# Current_Sink.net
KiCad netlist of a schematic drawn in Altium Designer
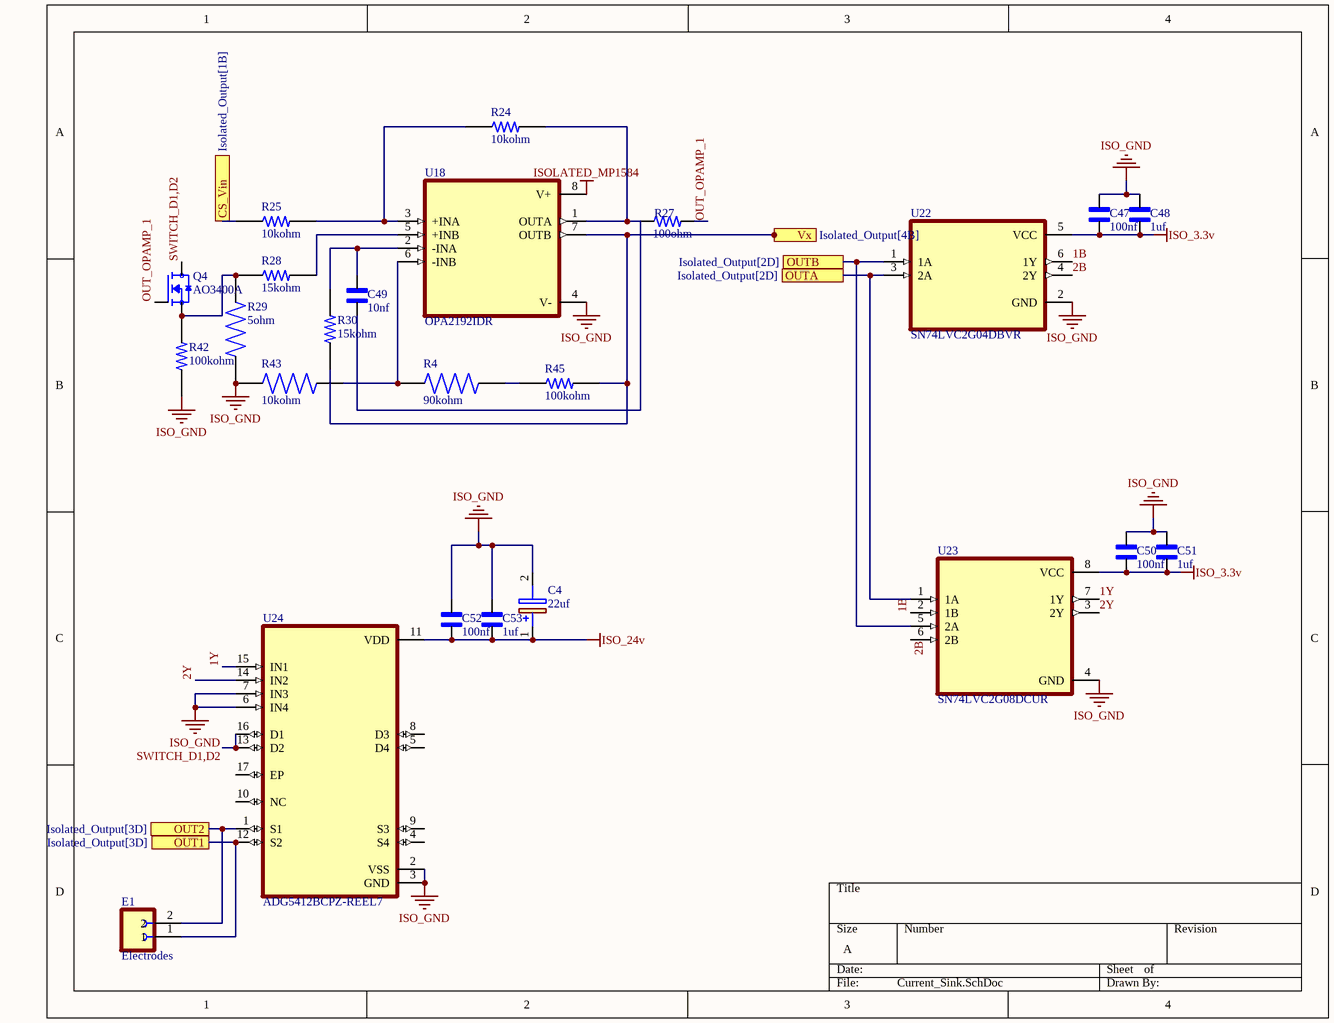
[diagram p0: Current_Sink.SchDoc]

(export (version "E")
  (design (tool "Eeschema 10.0.6"))
  (components
    (comp (ref "C4")
      (value "22uf")
      (footprint "SamacSys:CAPAE660X610N")
      (description "Capacitor Polarised")
      (fields
        (field (name "MANUFACTURER_PART_NUMBER") "HHXC500ARA220MF61G")
        (field (name "MOUSER PART NUMBER") "661-HHXC500A220MF61G")
      )
      (libsource (lib "*") (part "HHXC500ARA220MF61G"))
    )
    (comp (ref "C47")
      (value "100nf")
      (footprint "CAPC1608X90")
      (description "0603 1 nF 50 V Â±10 % Tolerance X7R Surface Mount Ceramic Capacitor")
      (fields (field (name "MF") "Yageo") (field (name "MP") "C0603KRX7R9BB102"))
      (libsource (lib "C0603KRX7R9BB102") (part "C0603KRX7R9BB102"))
    )
    (comp (ref "C48")
      (value "1uf")
      (footprint "CAPC1608X90")
      (description "0603 1 nF 50 V Â±10 % Tolerance X7R Surface Mount Ceramic Capacitor")
      (fields (field (name "MF") "Yageo") (field (name "MP") "C0603KRX7R9BB102"))
      (libsource (lib "C0603KRX7R9BB102") (part "C0603KRX7R9BB102"))
    )
    (comp (ref "C49")
      (value "10nf")
      (footprint "CAPC1608X90")
      (description "0603 1 nF 50 V Â±10 % Tolerance X7R Surface Mount Ceramic Capacitor")
      (fields (field (name "MF") "Yageo") (field (name "MP") "C0603KRX7R9BB102"))
      (libsource (lib "") (part "C0603KRX7R9BB102_1"))
    )
    (comp (ref "C50")
      (value "100nf")
      (footprint "CAPC1608X90")
      (description "0603 1 nF 50 V Â±10 % Tolerance X7R Surface Mount Ceramic Capacitor")
      (fields (field (name "MF") "Yageo") (field (name "MP") "C0603KRX7R9BB102"))
      (libsource (lib "C0603KRX7R9BB102") (part "C0603KRX7R9BB102"))
    )
    (comp (ref "C51")
      (value "1uf")
      (footprint "CAPC1608X90")
      (description "0603 1 nF 50 V Â±10 % Tolerance X7R Surface Mount Ceramic Capacitor")
      (fields (field (name "MF") "Yageo") (field (name "MP") "C0603KRX7R9BB102"))
      (libsource (lib "C0603KRX7R9BB102") (part "C0603KRX7R9BB102"))
    )
    (comp (ref "C52")
      (value "100nf")
      (footprint "CAPC1608X90")
      (description "0603 1 nF 50 V Â±10 % Tolerance X7R Surface Mount Ceramic Capacitor")
      (fields (field (name "MF") "Yageo") (field (name "MP") "C0603KRX7R9BB102"))
      (libsource (lib "C0603KRX7R9BB102") (part "C0603KRX7R9BB102"))
    )
    (comp (ref "C53")
      (value "1uf")
      (footprint "CAPC1608X90")
      (description "0603 1 nF 50 V Â±10 % Tolerance X7R Surface Mount Ceramic Capacitor")
      (fields (field (name "MF") "Yageo") (field (name "MP") "C0603KRX7R9BB102"))
      (libsource (lib "C0603KRX7R9BB102") (part "C0603KRX7R9BB102"))
    )
    (comp (ref "E1")
      (value "Electrodes")
      (footprint "JST_PHR-2")
      (description "PH Series 2 Position 2 mm Pitch Free Hanging Housing Connector")
      (fields (field (name "MP") "PHR-2"))
      (libsource (lib "PHR-2") (part "PHR-2"))
    )
    (comp (ref "Q4")
      (value "AO3400A")
      (footprint "SOT95P280X125-3N")
      (description "N-Channel 30 V 5.7A (Ta) 1.4W (Ta) Surface Mount SOT-23-3")
      (fields (field (name "MF") "Alpha & Omega Semiconductor"))
      (libsource (lib "AO3400A") (part "AO3400A"))
    )
    (comp (ref "R4")
      (value "90kohm")
      (footprint "RESC2012X65N")
      (description "5.11 Ohms Â±0.1% 0.25W, 1/4W Chip Resistor 0805 (2012 Metric) Automotive AEC-Q200 Thin Film")
      (fields (field (name "MF") "Stackpole Electronics Inc") (field (name "MP") "RNCF0805BTE5R11"))
      (libsource (lib "RNCF0805BTE5R11") (part "RNCF0805BTE5R11"))
    )
    (comp (ref "R24")
      (value "10kohm")
      (footprint "RESC1607X60N")
      (description "10 kOhms Â±5% 0.1W, 1/10W Chip Resistor 0603 (1608 Metric) Moisture Resistant Thick Film")
      (fields (field (name "MF") "Yageo") (field (name "MP") "RC0603JR-0710KL"))
      (libsource (lib "RC0603JR-0710KL") (part "RC0603JR-0710KL"))
    )
    (comp (ref "R25")
      (value "10kohm")
      (footprint "RESC1607X60N")
      (description "10 kOhms Â±5% 0.1W, 1/10W Chip Resistor 0603 (1608 Metric) Moisture Resistant Thick Film")
      (fields (field (name "MF") "Yageo") (field (name "MP") "RC0603JR-0710KL"))
      (libsource (lib "RC0603JR-0710KL") (part "RC0603JR-0710KL"))
    )
    (comp (ref "R27")
      (value "100ohm")
      (footprint "RESC1607X60N")
      (description "10 kOhms Â±5% 0.1W, 1/10W Chip Resistor 0603 (1608 Metric) Moisture Resistant Thick Film")
      (fields (field (name "MF") "Yageo") (field (name "MP") "RC0603JR-0710KL"))
      (libsource (lib "RC0603JR-0710KL") (part "RC0603JR-0710KL"))
    )
    (comp (ref "R28")
      (value "15kohm")
      (footprint "RESC1607X60N")
      (description "10 kOhms Â±5% 0.1W, 1/10W Chip Resistor 0603 (1608 Metric) Moisture Resistant Thick Film")
      (fields (field (name "MF") "Yageo") (field (name "MP") "RC0603JR-0710KL"))
      (libsource (lib "RC0603JR-0710KL") (part "RC0603JR-0710KL"))
    )
    (comp (ref "R29")
      (value "5ohm")
      (footprint "RESC2012X50N")
      (fields (field (name "MF") "Susumu") (field (name "MP") "RG2012V-103-P-T1"))
      (libsource (lib "RG2012V-103-P-T1") (part "RG2012V-103-P-T1"))
    )
    (comp (ref "R30")
      (value "15kohm")
      (footprint "RESC1607X60N")
      (description "10 kOhms Â±5% 0.1W, 1/10W Chip Resistor 0603 (1608 Metric) Moisture Resistant Thick Film")
      (fields (field (name "MF") "Yageo") (field (name "MP") "RC0603JR-0710KL"))
      (libsource (lib "RC0603JR-0710KL") (part "RC0603JR-0710KL"))
    )
    (comp (ref "R42")
      (value "100kohm")
      (footprint "RESC1607X60N")
      (description "10 kOhms Â±5% 0.1W, 1/10W Chip Resistor 0603 (1608 Metric) Moisture Resistant Thick Film")
      (fields (field (name "MF") "Yageo") (field (name "MP") "RC0603JR-0710KL"))
      (libsource (lib "RC0603JR-0710KL") (part "RC0603JR-0710KL"))
    )
    (comp (ref "R43")
      (value "10kohm")
      (footprint "RESC2012X50N")
      (fields (field (name "MF") "Susumu") (field (name "MP") "RG2012V-103-P-T1"))
      (libsource (lib "RG2012V-103-P-T1") (part "RG2012V-103-P-T1"))
    )
    (comp (ref "R45")
      (value "100kohm")
      (footprint "RESC1607X60N")
      (description "10 kOhms Â±5% 0.1W, 1/10W Chip Resistor 0603 (1608 Metric) Moisture Resistant Thick Film")
      (fields (field (name "MF") "Yageo") (field (name "MP") "RC0603JR-0710KL"))
      (libsource (lib "RC0603JR-0710KL") (part "RC0603JR-0710KL"))
    )
    (comp (ref "U18")
      (value "OPA2192IDR")
      (footprint "SOIC127P599X175-8N")
      (description "36-V, Precision, RRIO, Low Offset Voltage, Low Input Bias Current Op Amp With e-trim")
      (fields (field (name "MF") "Texas Instruments"))
      (libsource (lib "OPA2192IDR") (part "OPA2192IDR"))
    )
    (comp (ref "U22")
      (value "SN74LVC2G04DBVR")
      (footprint "SOT95P280X145-6N")
      (description "2-ch, 1.65-V to 5.5-V inverters")
      (fields (field (name "MF") "Texas Instruments"))
      (libsource (lib "SN74LVC2G04DBVR") (part "SN74LVC2G04DBVR"))
    )
    (comp (ref "U23")
      (value "SN74LVC2G08DCUR")
      (footprint "SOP50P310X90-8N")
      (description "2-ch, 2-input, 1.65-V to 5.5-V AND gates")
      (fields (field (name "MF") "Texas Instruments"))
      (libsource (lib "SN74LVC2G08DCUR") (part "SN74LVC2G08DCUR"))
    )
    (comp (ref "U24")
      (value "ADG5412BCPZ-REEL7")
      (footprint "QFN65P400X400X80-17N")
      (description "High Voltage Latch-Up Proof, Quad SPST Switches")
      (fields (field (name "MF") "Analog Devices"))
      (libsource (lib "ADG5412BCPZ-REEL7") (part "ADG5412BCPZ-REEL7"))
    )
  )
  (nets
    (net (code "1") (name "/1B") (class "Default")
      (node (ref "U22") (pin "6") (pinfunction "1Y_6") (pintype "output"))
      (node (ref "U23") (pin "2") (pinfunction "1B_2") (pintype "input"))
    )
    (net (code "2") (name "/1Y") (class "Default")
      (node (ref "U23") (pin "7") (pinfunction "1Y_7") (pintype "output"))
      (node (ref "U24") (pin "15") (pinfunction "IN1_15") (pintype "input"))
    )
    (net (code "3") (name "/2B") (class "Default")
      (node (ref "U22") (pin "4") (pinfunction "2Y_4") (pintype "output"))
      (node (ref "U23") (pin "6") (pinfunction "2B_6") (pintype "input"))
    )
    (net (code "4") (name "/2Y") (class "Default")
      (node (ref "U23") (pin "3") (pinfunction "2Y_3") (pintype "output"))
      (node (ref "U24") (pin "14") (pinfunction "IN2_14") (pintype "input"))
    )
    (net (code "5") (name "/CS_Vin") (class "Default")
      (node (ref "R25") (pin "1") (pinfunction "1_1") (pintype "passive"))
    )
    (net (code "6") (name "/OUT1") (class "Default")
      (node (ref "E1") (pin "1") (pinfunction "1_1") (pintype "passive"))
      (node (ref "U24") (pin "12") (pinfunction "S2_12") (pintype "bidirectional"))
    )
    (net (code "7") (name "/OUT2") (class "Default")
      (node (ref "E1") (pin "2") (pinfunction "2_2") (pintype "passive"))
      (node (ref "U24") (pin "1") (pinfunction "S1_1") (pintype "bidirectional"))
    )
    (net (code "8") (name "/OUTA") (class "Default")
      (node (ref "U22") (pin "3") (pinfunction "2A_3") (pintype "input"))
      (node (ref "U23") (pin "1") (pinfunction "1A_1") (pintype "input"))
    )
    (net (code "9") (name "/OUTB") (class "Default")
      (node (ref "U22") (pin "1") (pinfunction "1A_1") (pintype "input"))
      (node (ref "U23") (pin "5") (pinfunction "2A_5") (pintype "input"))
    )
    (net (code "10") (name "/OUT_OPAMP_1") (class "Default")
      (node (ref "Q4") (pin "1") (pinfunction "G_1") (pintype "passive"))
      (node (ref "R27") (pin "2") (pinfunction "2_2") (pintype "passive"))
    )
    (net (code "11") (name "/SWITCH_D1,D2") (class "Default")
      (node (ref "Q4") (pin "3") (pinfunction "D_3") (pintype "passive"))
      (node (ref "U24") (pin "13") (pinfunction "D2_13") (pintype "bidirectional"))
      (node (ref "U24") (pin "16") (pinfunction "D1_16") (pintype "bidirectional"))
    )
    (net (code "12") (name "/Vx") (class "Default")
      (node (ref "R30") (pin "1") (pinfunction "1_1") (pintype "passive"))
      (node (ref "R45") (pin "2") (pinfunction "2_2") (pintype "passive"))
      (node (ref "U18") (pin "7") (pinfunction "OUTB_7") (pintype "output"))
    )
    (net (code "13") (name "ISOLATED_MP1584") (class "Default")
      (node (ref "U18") (pin "8") (pinfunction "V+_8") (pintype "power_in"))
    )
    (net (code "14") (name "ISO_3.3v") (class "Default")
      (node (ref "C47") (pin "1") (pinfunction "1_1") (pintype "passive"))
      (node (ref "C48") (pin "1") (pinfunction "1_1") (pintype "passive"))
      (node (ref "C50") (pin "1") (pinfunction "1_1") (pintype "passive"))
      (node (ref "C51") (pin "1") (pinfunction "1_1") (pintype "passive"))
      (node (ref "U22") (pin "5") (pinfunction "VCC_5") (pintype "power_in"))
      (node (ref "U23") (pin "8") (pinfunction "VCC_8") (pintype "power_in"))
    )
    (net (code "15") (name "ISO_24v") (class "Default")
      (node (ref "C4") (pin "1") (pinfunction "+_1") (pintype "passive"))
      (node (ref "C52") (pin "1") (pinfunction "1_1") (pintype "passive"))
      (node (ref "C53") (pin "1") (pinfunction "1_1") (pintype "passive"))
      (node (ref "U24") (pin "11") (pinfunction "VDD_11") (pintype "power_in"))
    )
    (net (code "16") (name "ISO_GND") (class "Default")
      (node (ref "C4") (pin "2") (pinfunction "-_2") (pintype "passive"))
      (node (ref "C47") (pin "2") (pinfunction "2_2") (pintype "passive"))
      (node (ref "C48") (pin "2") (pinfunction "2_2") (pintype "passive"))
      (node (ref "C50") (pin "2") (pinfunction "2_2") (pintype "passive"))
      (node (ref "C51") (pin "2") (pinfunction "2_2") (pintype "passive"))
      (node (ref "C52") (pin "2") (pinfunction "2_2") (pintype "passive"))
      (node (ref "C53") (pin "2") (pinfunction "2_2") (pintype "passive"))
      (node (ref "R29") (pin "1") (pinfunction "1_1") (pintype "passive"))
      (node (ref "R42") (pin "1") (pinfunction "1_1") (pintype "passive"))
      (node (ref "R43") (pin "1") (pinfunction "1_1") (pintype "passive"))
      (node (ref "U18") (pin "4") (pinfunction "V-_4") (pintype "power_in"))
      (node (ref "U22") (pin "2") (pinfunction "GND_2") (pintype "power_in"))
      (node (ref "U23") (pin "4") (pinfunction "GND_4") (pintype "power_in"))
      (node (ref "U24") (pin "2") (pinfunction "VSS_2") (pintype "power_in"))
      (node (ref "U24") (pin "3") (pinfunction "GND_3") (pintype "power_in"))
      (node (ref "U24") (pin "6") (pinfunction "IN4_6") (pintype "input"))
      (node (ref "U24") (pin "7") (pinfunction "IN3_7") (pintype "input"))
    )
    (net (code "17") (name "Net-(Q4-S)") (class "Default")
      (node (ref "Q4") (pin "2") (pinfunction "S_2") (pintype "passive"))
      (node (ref "R28") (pin "1") (pinfunction "1_1") (pintype "passive"))
      (node (ref "R29") (pin "2") (pinfunction "2_2") (pintype "passive"))
      (node (ref "R42") (pin "2") (pinfunction "2_2") (pintype "passive"))
    )
    (net (code "18") (name "Net-(R4-Pad2)") (class "Default")
      (node (ref "R4") (pin "2") (pinfunction "2_2") (pintype "passive"))
      (node (ref "R45") (pin "1") (pinfunction "1_1") (pintype "passive"))
    )
    (net (code "19") (name "Net-(U18-+INA)") (class "Default")
      (node (ref "R24") (pin "1") (pinfunction "1_1") (pintype "passive"))
      (node (ref "R25") (pin "2") (pinfunction "2_2") (pintype "passive"))
      (node (ref "U18") (pin "3") (pinfunction "+INA_3") (pintype "input"))
    )
    (net (code "20") (name "Net-(U18-+INB)") (class "Default")
      (node (ref "R28") (pin "2") (pinfunction "2_2") (pintype "passive"))
      (node (ref "U18") (pin "5") (pinfunction "+INB_5") (pintype "input"))
    )
    (net (code "21") (name "Net-(U18--INA)") (class "Default")
      (node (ref "C49") (pin "1") (pinfunction "1_1") (pintype "passive"))
      (node (ref "R30") (pin "2") (pinfunction "2_2") (pintype "passive"))
      (node (ref "U18") (pin "2") (pinfunction "-INA_2") (pintype "input"))
    )
    (net (code "22") (name "Net-(U18--INB)") (class "Default")
      (node (ref "R4") (pin "1") (pinfunction "1_1") (pintype "passive"))
      (node (ref "R43") (pin "2") (pinfunction "2_2") (pintype "passive"))
      (node (ref "U18") (pin "6") (pinfunction "-INB_6") (pintype "input"))
    )
    (net (code "23") (name "Net-(U18-OUTA)") (class "Default")
      (node (ref "C49") (pin "2") (pinfunction "2_2") (pintype "passive"))
      (node (ref "R24") (pin "2") (pinfunction "2_2") (pintype "passive"))
      (node (ref "R27") (pin "1") (pinfunction "1_1") (pintype "passive"))
      (node (ref "U18") (pin "1") (pinfunction "OUTA_1") (pintype "output"))
    )
    (net (code "24") (name "unconnected-(U24-D3-Pad8)") (class "Default")
      (node (ref "U24") (pin "8") (pinfunction "D3_8") (pintype "bidirectional"))
    )
    (net (code "25") (name "unconnected-(U24-D4-Pad5)") (class "Default")
      (node (ref "U24") (pin "5") (pinfunction "D4_5") (pintype "bidirectional"))
    )
    (net (code "26") (name "unconnected-(U24-EP-Pad17)") (class "Default")
      (node (ref "U24") (pin "17") (pinfunction "EP_17") (pintype "bidirectional"))
    )
    (net (code "27") (name "unconnected-(U24-NC-Pad10)") (class "Default")
      (node (ref "U24") (pin "10") (pinfunction "NC_10") (pintype "bidirectional"))
    )
    (net (code "28") (name "unconnected-(U24-S3-Pad9)") (class "Default")
      (node (ref "U24") (pin "9") (pinfunction "S3_9") (pintype "bidirectional"))
    )
    (net (code "29") (name "unconnected-(U24-S4-Pad4)") (class "Default")
      (node (ref "U24") (pin "4") (pinfunction "S4_4") (pintype "bidirectional"))
    )
  )
)
